# Thing_Plus_ESP32_C6.net
KiCad netlist of a schematic drawn in EAGLE
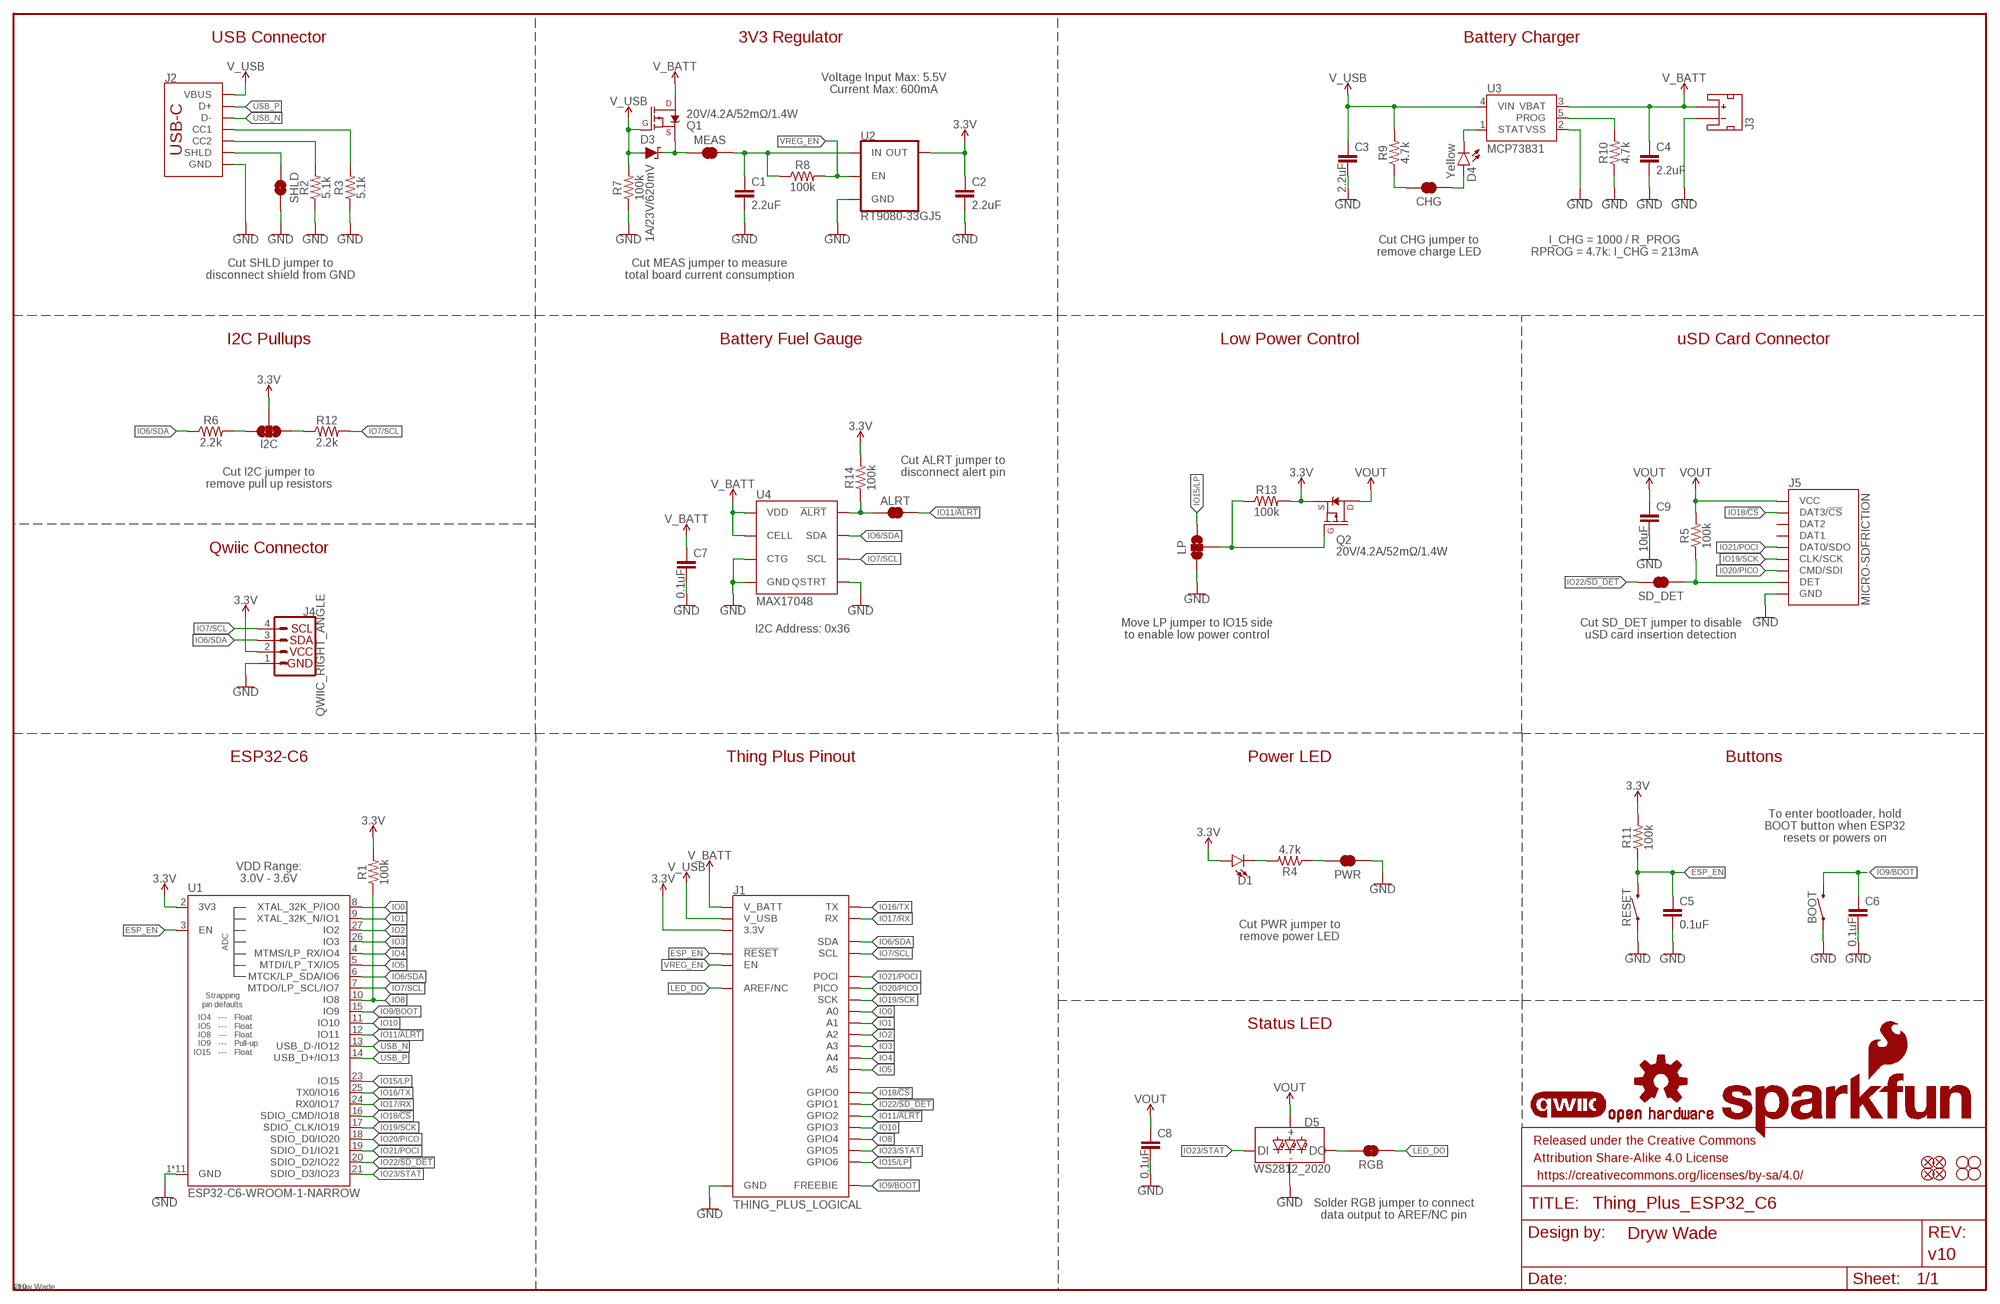
[diagram p0: schematic, sheet 1]

(export (version "E")
  (design (tool "Eeschema 10.0.6"))
  (components
    (comp (ref "ALRT")
      (value "JUMPER-SMT_2_NC_TRACE_SILK")
      (footprint "eagle-import:SMT-JUMPER_2_NC_TRACE_SILK")
      (libsource (lib "eagle-import") (part "JUMPER-SMT_2_NC_TRACE_SILK"))
    )
    (comp (ref "BOOT")
      (value "MOMENTARY-SWITCH-SPST-SMD-4.6X2.8MM")
      (footprint "eagle-import:TACTILE_SWITCH_SMD_4.6X2.8MM")
      (libsource (lib "eagle-import") (part "MOMENTARY-SWITCH-SPST-SMD-4.6X2.8MM"))
    )
    (comp (ref "C1")
      (value "2.2uF")
      (footprint "eagle-import:0603")
      (libsource (lib "eagle-import") (part "2.2UF-0603-10V-20%"))
    )
    (comp (ref "C2")
      (value "2.2uF")
      (footprint "eagle-import:0603")
      (libsource (lib "eagle-import") (part "2.2UF-0603-10V-20%"))
    )
    (comp (ref "C3")
      (value "2.2uF")
      (footprint "eagle-import:0603")
      (libsource (lib "eagle-import") (part "2.2UF-0603-10V-20%"))
    )
    (comp (ref "C4")
      (value "2.2uF")
      (footprint "eagle-import:0603")
      (libsource (lib "eagle-import") (part "2.2UF-0603-10V-20%"))
    )
    (comp (ref "C5")
      (value "0.1uF")
      (footprint "eagle-import:0603")
      (libsource (lib "eagle-import") (part "0.1UF-0603-25V-(+80/-20%)"))
    )
    (comp (ref "C6")
      (value "0.1uF")
      (footprint "eagle-import:0603")
      (libsource (lib "eagle-import") (part "0.1UF-0603-25V-(+80/-20%)"))
    )
    (comp (ref "C7")
      (value "0.1uF")
      (footprint "eagle-import:0603")
      (libsource (lib "eagle-import") (part "0.1UF-0603-25V-(+80/-20%)"))
    )
    (comp (ref "C8")
      (value "0.1uF")
      (footprint "eagle-import:0603")
      (libsource (lib "eagle-import") (part "0.1UF-0603-25V-(+80/-20%)"))
    )
    (comp (ref "C9")
      (value "10uF")
      (footprint "eagle-import:0603")
      (libsource (lib "eagle-import") (part "10UF-0603-6.3V-20%"))
    )
    (comp (ref "CHG")
      (value "JUMPER-SMT_2_NC_TRACE_SILK")
      (footprint "eagle-import:SMT-JUMPER_2_NC_TRACE_SILK")
      (libsource (lib "eagle-import") (part "JUMPER-SMT_2_NC_TRACE_SILK"))
    )
    (comp (ref "D1")
      (value "LED-RED_0603-KB")
      (footprint "eagle-import:LED-0603")
      (libsource (lib "eagle-import") (part "LED-RED_0603-KB"))
    )
    (comp (ref "D3")
      (value "1A/23V/620mV")
      (footprint "eagle-import:SOD-323")
      (libsource (lib "eagle-import") (part "DIODE-SCHOTTKY-BAT20J"))
    )
    (comp (ref "D4")
      (value "Yellow")
      (footprint "eagle-import:LED-0603")
      (libsource (lib "eagle-import") (part "LED-YELLOW0603"))
    )
    (comp (ref "D5")
      (value "WS2812_2020")
      (footprint "eagle-import:WS2812-2020")
      (libsource (lib "eagle-import") (part "WS2812_2020"))
    )
    (comp (ref "FD1")
      (value "FIDUCIALUFIDUCIAL")
      (footprint "eagle-import:FIDUCIAL-MICRO")
      (libsource (lib "eagle-import") (part "FIDUCIALUFIDUCIAL"))
    )
    (comp (ref "FD2")
      (value "FIDUCIALUFIDUCIAL")
      (footprint "eagle-import:FIDUCIAL-MICRO")
      (libsource (lib "eagle-import") (part "FIDUCIALUFIDUCIAL"))
    )
    (comp (ref "FD3")
      (value "FIDUCIALUFIDUCIAL")
      (footprint "eagle-import:FIDUCIAL-MICRO")
      (libsource (lib "eagle-import") (part "FIDUCIALUFIDUCIAL"))
    )
    (comp (ref "FD4")
      (value "FIDUCIALUFIDUCIAL")
      (footprint "eagle-import:FIDUCIAL-MICRO")
      (libsource (lib "eagle-import") (part "FIDUCIALUFIDUCIAL"))
    )
    (comp (ref "FRAME1")
      (value "FRAME-LEDGER")
      (footprint "eagle-import:CREATIVE_COMMONS")
      (fields (field (name "DESIGNER") "Dryw Wade") (field (name "REV") "v10"))
      (libsource (lib "eagle-import") (part "FRAME-LEDGER"))
    )
    (comp (ref "H1")
      (value "STAND-OFF")
      (footprint "eagle-import:STAND-OFF")
      (libsource (lib "eagle-import") (part "STAND-OFF"))
    )
    (comp (ref "H2")
      (value "STAND-OFF")
      (footprint "eagle-import:STAND-OFF")
      (libsource (lib "eagle-import") (part "STAND-OFF"))
    )
    (comp (ref "H3")
      (value "STAND-OFF")
      (footprint "eagle-import:STAND-OFF")
      (libsource (lib "eagle-import") (part "STAND-OFF"))
    )
    (comp (ref "H4")
      (value "STAND-OFF")
      (footprint "eagle-import:STAND-OFF")
      (libsource (lib "eagle-import") (part "STAND-OFF"))
    )
    (comp (ref "I2C")
      (value "JUMPER-SMT_3_2-NC_TRACE_SILK")
      (footprint "eagle-import:SMT-JUMPER_3_2-NC_TRACE_SILK")
      (libsource (lib "eagle-import") (part "JUMPER-SMT_3_2-NC_TRACE_SILK"))
    )
    (comp (ref "J1")
      (value "THING_PLUS_LOGICAL")
      (footprint "eagle-import:THING_PLUS")
      (libsource (lib "eagle-import") (part "THING_PLUS_LOGICAL"))
    )
    (comp (ref "J2")
      (value "USB_C_4-LAYER_PADS")
      (footprint "eagle-import:USB-C-16P_4LAYER-PADS")
      (libsource (lib "eagle-import") (part "USB_C_4-LAYER_PADS"))
    )
    (comp (ref "J3")
      (value "JST_2MM_MALE")
      (footprint "eagle-import:JST-2-SMD")
      (libsource (lib "eagle-import") (part "JST_2MM_MALE"))
    )
    (comp (ref "J4")
      (value "QWIIC_RIGHT_ANGLE")
      (footprint "eagle-import:JST04_1MM_RA")
      (libsource (lib "eagle-import") (part "QWIIC_CONNECTORJS-1MM"))
    )
    (comp (ref "J5")
      (value "MICRO-SDFRICTION")
      (footprint "eagle-import:MICROSD_TINY")
      (libsource (lib "eagle-import") (part "MICRO-SDFRICTION"))
    )
    (comp (ref "LOGO1")
      (value "SFE_LOGO_NAME_FLAME.1_INCH")
      (footprint "eagle-import:SFE_LOGO_NAME_FLAME_.1")
      (libsource (lib "eagle-import") (part "SFE_LOGO_NAME_FLAME.1_INCH"))
    )
    (comp (ref "LOGO2")
      (value "QWIIC_LOGO_4MM")
      (footprint "eagle-import:QWIIC_4MM")
      (libsource (lib "eagle-import") (part "QWIIC_LOGO_4MM"))
    )
    (comp (ref "LOGO3")
      (value "OSHW-LOGOM")
      (footprint "eagle-import:OSHW-LOGO-M")
      (libsource (lib "eagle-import") (part "OSHW-LOGOM"))
    )
    (comp (ref "LP")
      (value "JUMPER-SMT_3_1-NC_TRACE_SILK")
      (footprint "eagle-import:SMT-JUMPER_3_1-NC_TRACE_SILK")
      (libsource (lib "eagle-import") (part "JUMPER-SMT_3_1-NC_TRACE_SILK"))
    )
    (comp (ref "MEAS")
      (value "JUMPER-COMBO_2_NC_TRACE")
      (footprint "eagle-import:COMBO-JUMPER_2_NC_TRACE")
      (libsource (lib "eagle-import") (part "JUMPER-COMBO_2_NC_TRACE"))
    )
    (comp (ref "PWR")
      (value "JUMPER-SMT_2_NC_TRACE_SILK")
      (footprint "eagle-import:SMT-JUMPER_2_NC_TRACE_SILK")
      (libsource (lib "eagle-import") (part "JUMPER-SMT_2_NC_TRACE_SILK"))
    )
    (comp (ref "Q1")
      (value "20V/4.2A/52mΩ/1.4W")
      (footprint "eagle-import:SOT23-3")
      (libsource (lib "eagle-import") (part "MOSFET_PCH-DMG2305UX-7"))
    )
    (comp (ref "Q2")
      (value "20V/4.2A/52mΩ/1.4W")
      (footprint "eagle-import:SOT23-3")
      (libsource (lib "eagle-import") (part "MOSFET_PCH-DMG2305UX-7"))
    )
    (comp (ref "R1")
      (value "100k")
      (footprint "eagle-import:0603")
      (libsource (lib "eagle-import") (part "100KOHM-0603-1/10W-1%"))
    )
    (comp (ref "R2")
      (value "5.1k")
      (footprint "eagle-import:0603")
      (libsource (lib "eagle-import") (part "5.1KOHM5.1KOHM-0603-1/10W-1%"))
    )
    (comp (ref "R3")
      (value "5.1k")
      (footprint "eagle-import:0603")
      (libsource (lib "eagle-import") (part "5.1KOHM5.1KOHM-0603-1/10W-1%"))
    )
    (comp (ref "R4")
      (value "4.7k")
      (footprint "eagle-import:0603")
      (libsource (lib "eagle-import") (part "4.7KOHM-0603-1/10W-1%"))
    )
    (comp (ref "R5")
      (value "100k")
      (footprint "eagle-import:0603")
      (libsource (lib "eagle-import") (part "100KOHM-0603-1/10W-1%"))
    )
    (comp (ref "R6")
      (value "2.2k")
      (footprint "eagle-import:0603")
      (libsource (lib "eagle-import") (part "2.2KOHM-0603-1/10W-1%"))
    )
    (comp (ref "R7")
      (value "100k")
      (footprint "eagle-import:0603")
      (libsource (lib "eagle-import") (part "100KOHM-0603-1/10W-1%"))
    )
    (comp (ref "R8")
      (value "100k")
      (footprint "eagle-import:0603")
      (libsource (lib "eagle-import") (part "100KOHM-0603-1/10W-1%"))
    )
    (comp (ref "R9")
      (value "4.7k")
      (footprint "eagle-import:0603")
      (libsource (lib "eagle-import") (part "4.7KOHM-0603-1/10W-1%"))
    )
    (comp (ref "R10")
      (value "4.7k")
      (footprint "eagle-import:0603")
      (libsource (lib "eagle-import") (part "4.7KOHM-0603-1/10W-1%"))
    )
    (comp (ref "R11")
      (value "100k")
      (footprint "eagle-import:0603")
      (libsource (lib "eagle-import") (part "100KOHM-0603-1/10W-1%"))
    )
    (comp (ref "R12")
      (value "2.2k")
      (footprint "eagle-import:0603")
      (libsource (lib "eagle-import") (part "2.2KOHM-0603-1/10W-1%"))
    )
    (comp (ref "R13")
      (value "100k")
      (footprint "eagle-import:0603")
      (libsource (lib "eagle-import") (part "100KOHM-0603-1/10W-1%"))
    )
    (comp (ref "R14")
      (value "100k")
      (footprint "eagle-import:0603")
      (libsource (lib "eagle-import") (part "100KOHM-0603-1/10W-1%"))
    )
    (comp (ref "RESET")
      (value "MOMENTARY-SWITCH-SPST-SMD-4.6X2.8MM")
      (footprint "eagle-import:TACTILE_SWITCH_SMD_4.6X2.8MM")
      (libsource (lib "eagle-import") (part "MOMENTARY-SWITCH-SPST-SMD-4.6X2.8MM"))
    )
    (comp (ref "RGB")
      (value "JUMPER-SMT_2_NO_SILK")
      (footprint "eagle-import:SMT-JUMPER_2_NO_SILK")
      (libsource (lib "eagle-import") (part "JUMPER-SMT_2_NO_SILK"))
    )
    (comp (ref "SD_DET")
      (value "JUMPER-SMT_2_NC_TRACE_SILK")
      (footprint "eagle-import:SMT-JUMPER_2_NC_TRACE_SILK")
      (libsource (lib "eagle-import") (part "JUMPER-SMT_2_NC_TRACE_SILK"))
    )
    (comp (ref "SHLD")
      (value "JUMPER-SMT_2_NC_TRACE_SILK")
      (footprint "eagle-import:SMT-JUMPER_2_NC_TRACE_SILK")
      (libsource (lib "eagle-import") (part "JUMPER-SMT_2_NC_TRACE_SILK"))
    )
    (comp (ref "U1")
      (value "ESP32-C6-WROOM-1-NARROW")
      (footprint "eagle-import:ESP32-C6-WROOM-1-NARROW")
      (libsource (lib "eagle-import") (part "ESP32-C6-WROOM-1-NARROW"))
    )
    (comp (ref "U2")
      (value "RT9080-33GJ5")
      (footprint "eagle-import:SOT23-5")
      (libsource (lib "eagle-import") (part "V_REG_RT9080"))
    )
    (comp (ref "U3")
      (value "MCP73831")
      (footprint "eagle-import:SOT23-5")
      (libsource (lib "eagle-import") (part "MCP73831"))
    )
    (comp (ref "U4")
      (value "MAX17048")
      (footprint "eagle-import:DFN-8")
      (libsource (lib "eagle-import") (part "MAX17048DFN8"))
    )
  )
  (nets
    (net (code "1") (name "/IO11{slash}~{ALRT}") (class "Default")
      (node (ref "ALRT") (pin "2") (pinfunction "2_2") (pintype "passive"))
      (node (ref "J1") (pin "7") (pinfunction "GPIO2_7") (pintype "bidirectional"))
      (node (ref "U1") (pin "12") (pinfunction "IO11_12") (pintype "bidirectional"))
    )
    (net (code "2") (name "/IO18{slash}~{CS}") (class "Default")
      (node (ref "J1") (pin "9") (pinfunction "GPIO0_9") (pintype "bidirectional"))
      (node (ref "J5") (pin "2") (pinfunction "DAT3/~{CS}_2") (pintype "bidirectional"))
      (node (ref "U1") (pin "16") (pinfunction "SDIO_CMD/IO18_16") (pintype "bidirectional"))
    )
    (net (code "3") (name "/IO22{slash}~{SD_DET}") (class "Default")
      (node (ref "J1") (pin "8") (pinfunction "GPIO1_8") (pintype "bidirectional"))
      (node (ref "SD_DET") (pin "2") (pinfunction "2_2") (pintype "passive"))
      (node (ref "U1") (pin "20") (pinfunction "SDIO_D2/IO22_20") (pintype "bidirectional"))
    )
    (net (code "4") (name "3.3V") (class "Default")
      (node (ref "C2") (pin "1") (pinfunction "1_1") (pintype "passive"))
      (node (ref "D1") (pin "A") (pinfunction "A_A") (pintype "passive"))
      (node (ref "I2C") (pin "2") (pinfunction "2_2") (pintype "passive"))
      (node (ref "J1") (pin "27") (pinfunction "3.3V_27") (pintype "bidirectional"))
      (node (ref "J4") (pin "2") (pinfunction "2_2") (pintype "power_in"))
      (node (ref "Q2") (pin "2") (pinfunction "S_2") (pintype "bidirectional"))
      (node (ref "R1") (pin "2") (pinfunction "2_2") (pintype "passive"))
      (node (ref "R11") (pin "2") (pinfunction "2_2") (pintype "passive"))
      (node (ref "R13") (pin "2") (pinfunction "2_2") (pintype "passive"))
      (node (ref "R14") (pin "2") (pinfunction "2_2") (pintype "passive"))
      (node (ref "U1") (pin "2") (pinfunction "3V3_2") (pintype "bidirectional"))
      (node (ref "U2") (pin "5") (pinfunction "OUT_5") (pintype "passive"))
    )
    (net (code "5") (name "ESP_EN") (class "Default")
      (node (ref "C5") (pin "1") (pinfunction "1_1") (pintype "passive"))
      (node (ref "J1") (pin "28") (pinfunction "~{RESET}_28") (pintype "bidirectional"))
      (node (ref "R11") (pin "1") (pinfunction "1_1") (pintype "passive"))
      (node (ref "RESET") (pin "3") (pinfunction "2_3") (pintype "passive"))
      (node (ref "RESET") (pin "4") (pinfunction "2_4") (pintype "passive"))
      (node (ref "U1") (pin "3") (pinfunction "EN_3") (pintype "bidirectional"))
    )
    (net (code "6") (name "GND") (class "Default")
      (node (ref "BOOT") (pin "1") (pinfunction "1_1") (pintype "passive"))
      (node (ref "BOOT") (pin "2") (pinfunction "1_2") (pintype "passive"))
      (node (ref "C1") (pin "2") (pinfunction "2_2") (pintype "passive"))
      (node (ref "C2") (pin "2") (pinfunction "2_2") (pintype "passive"))
      (node (ref "C3") (pin "2") (pinfunction "2_2") (pintype "passive"))
      (node (ref "C4") (pin "2") (pinfunction "2_2") (pintype "passive"))
      (node (ref "C5") (pin "2") (pinfunction "2_2") (pintype "passive"))
      (node (ref "C6") (pin "2") (pinfunction "2_2") (pintype "passive"))
      (node (ref "C7") (pin "2") (pinfunction "2_2") (pintype "passive"))
      (node (ref "C8") (pin "2") (pinfunction "2_2") (pintype "passive"))
      (node (ref "C9") (pin "2") (pinfunction "2_2") (pintype "passive"))
      (node (ref "D5") (pin "GND") (pinfunction "GND_GND") (pintype "bidirectional"))
      (node (ref "J1") (pin "25") (pinfunction "GND_25") (pintype "bidirectional"))
      (node (ref "J2") (pin "GND") (pinfunction "GND_GND") (pintype "bidirectional"))
      (node (ref "J2") (pin "GND2") (pinfunction "GND_GND2") (pintype "bidirectional"))
      (node (ref "J3") (pin "1") (pinfunction "-_1") (pintype "bidirectional"))
      (node (ref "J4") (pin "1") (pinfunction "1_1") (pintype "power_in"))
      (node (ref "J5") (pin "6") (pinfunction "GND_6") (pintype "bidirectional"))
      (node (ref "J5") (pin "GND1") (pinfunction "GND_GND1") (pintype "bidirectional"))
      (node (ref "J5") (pin "GND2") (pinfunction "GND_GND2") (pintype "bidirectional"))
      (node (ref "J5") (pin "GND3") (pinfunction "GND_GND3") (pintype "bidirectional"))
      (node (ref "J5") (pin "GND4") (pinfunction "GND_GND4") (pintype "bidirectional"))
      (node (ref "J5") (pin "GND5") (pinfunction "GND_GND5") (pintype "bidirectional"))
      (node (ref "J5") (pin "GND6") (pinfunction "GND_GND6") (pintype "bidirectional"))
      (node (ref "LP") (pin "3") (pinfunction "3_3") (pintype "passive"))
      (node (ref "PWR") (pin "1") (pinfunction "1_1") (pintype "passive"))
      (node (ref "R10") (pin "1") (pinfunction "1_1") (pintype "passive"))
      (node (ref "R2") (pin "1") (pinfunction "1_1") (pintype "passive"))
      (node (ref "R3") (pin "1") (pinfunction "1_1") (pintype "passive"))
      (node (ref "R7") (pin "1") (pinfunction "1_1") (pintype "passive"))
      (node (ref "RESET") (pin "1") (pinfunction "1_1") (pintype "passive"))
      (node (ref "RESET") (pin "2") (pinfunction "1_2") (pintype "passive"))
      (node (ref "SHLD") (pin "2") (pinfunction "2_2") (pintype "passive"))
      (node (ref "U1") (pin "1") (pinfunction "GND_1") (pintype "bidirectional"))
      (node (ref "U1") (pin "28") (pinfunction "GND_28") (pintype "bidirectional"))
      (node (ref "U1") (pin "29") (pinfunction "GND_29") (pintype "bidirectional"))
      (node (ref "U1") (pin "30") (pinfunction "GND_30") (pintype "bidirectional"))
      (node (ref "U1") (pin "31") (pinfunction "GND_31") (pintype "bidirectional"))
      (node (ref "U1") (pin "32") (pinfunction "GND_32") (pintype "bidirectional"))
      (node (ref "U1") (pin "33") (pinfunction "GND_33") (pintype "bidirectional"))
      (node (ref "U1") (pin "34") (pinfunction "GND_34") (pintype "bidirectional"))
      (node (ref "U1") (pin "35") (pinfunction "GND_35") (pintype "bidirectional"))
      (node (ref "U1") (pin "36") (pinfunction "GND_36") (pintype "bidirectional"))
      (node (ref "U1") (pin "37") (pinfunction "GND_37") (pintype "bidirectional"))
      (node (ref "U2") (pin "2") (pinfunction "GND_2") (pintype "input"))
      (node (ref "U3") (pin "2") (pinfunction "VSS_2") (pintype "power_in"))
      (node (ref "U4") (pin "1") (pinfunction "CTG_1") (pintype "input"))
      (node (ref "U4") (pin "4") (pinfunction "GND_4") (pintype "bidirectional"))
      (node (ref "U4") (pin "6") (pinfunction "QSTRT_6") (pintype "bidirectional"))
      (node (ref "U4") (pin "9") (pinfunction "GND_9") (pintype "bidirectional"))
    )
    (net (code "7") (name "IO0") (class "Default")
      (node (ref "J1") (pin "24") (pinfunction "A0_24") (pintype "bidirectional"))
      (node (ref "U1") (pin "8") (pinfunction "XTAL_32K_P/IO0_8") (pintype "bidirectional"))
    )
    (net (code "8") (name "IO1") (class "Default")
      (node (ref "J1") (pin "23") (pinfunction "A1_23") (pintype "bidirectional"))
      (node (ref "U1") (pin "9") (pinfunction "XTAL_32K_N/IO1_9") (pintype "bidirectional"))
    )
    (net (code "9") (name "IO2") (class "Default")
      (node (ref "J1") (pin "22") (pinfunction "A2_22") (pintype "bidirectional"))
      (node (ref "U1") (pin "27") (pinfunction "IO2_27") (pintype "bidirectional"))
    )
    (net (code "10") (name "IO3") (class "Default")
      (node (ref "J1") (pin "21") (pinfunction "A3_21") (pintype "bidirectional"))
      (node (ref "U1") (pin "26") (pinfunction "IO3_26") (pintype "bidirectional"))
    )
    (net (code "11") (name "IO4") (class "Default")
      (node (ref "J1") (pin "20") (pinfunction "A4_20") (pintype "bidirectional"))
      (node (ref "U1") (pin "4") (pinfunction "MTMS/LP_RX/IO4_4") (pintype "bidirectional"))
    )
    (net (code "12") (name "IO5") (class "Default")
      (node (ref "J1") (pin "19") (pinfunction "A5_19") (pintype "bidirectional"))
      (node (ref "U1") (pin "5") (pinfunction "MTDI/LP_TX/IO5_5") (pintype "bidirectional"))
    )
    (net (code "13") (name "IO6{slash}SDA") (class "Default")
      (node (ref "J1") (pin "1") (pinfunction "SDA_1") (pintype "bidirectional"))
      (node (ref "J4") (pin "3") (pinfunction "3_3") (pintype "passive"))
      (node (ref "R6") (pin "1") (pinfunction "1_1") (pintype "passive"))
      (node (ref "U1") (pin "6") (pinfunction "MTCK/LP_SDA/IO6_6") (pintype "bidirectional"))
      (node (ref "U4") (pin "8") (pinfunction "SDA_8") (pintype "input"))
    )
    (net (code "14") (name "IO7{slash}SCL") (class "Default")
      (node (ref "J1") (pin "2") (pinfunction "SCL_2") (pintype "bidirectional"))
      (node (ref "J4") (pin "4") (pinfunction "4_4") (pintype "passive"))
      (node (ref "R12") (pin "2") (pinfunction "2_2") (pintype "passive"))
      (node (ref "U1") (pin "7") (pinfunction "MTDO/LP_SCL/IO7_7") (pintype "bidirectional"))
      (node (ref "U4") (pin "7") (pinfunction "SCL_7") (pintype "output"))
    )
    (net (code "15") (name "IO8") (class "Default")
      (node (ref "J1") (pin "5") (pinfunction "GPIO4_5") (pintype "bidirectional"))
      (node (ref "R1") (pin "1") (pinfunction "1_1") (pintype "passive"))
      (node (ref "U1") (pin "10") (pinfunction "IO8_10") (pintype "bidirectional"))
    )
    (net (code "16") (name "IO9{slash}BOOT") (class "Default")
      (node (ref "BOOT") (pin "3") (pinfunction "2_3") (pintype "passive"))
      (node (ref "BOOT") (pin "4") (pinfunction "2_4") (pintype "passive"))
      (node (ref "C6") (pin "1") (pinfunction "1_1") (pintype "passive"))
      (node (ref "J1") (pin "13") (pinfunction "FREEBIE_13") (pintype "bidirectional"))
      (node (ref "U1") (pin "15") (pinfunction "IO9_15") (pintype "bidirectional"))
    )
    (net (code "17") (name "IO10") (class "Default")
      (node (ref "J1") (pin "6") (pinfunction "GPIO3_6") (pintype "bidirectional"))
      (node (ref "U1") (pin "11") (pinfunction "IO10_11") (pintype "bidirectional"))
    )
    (net (code "18") (name "IO15{slash}LP") (class "Default")
      (node (ref "J1") (pin "3") (pinfunction "GPIO6_3") (pintype "bidirectional"))
      (node (ref "LP") (pin "1") (pinfunction "1_1") (pintype "passive"))
      (node (ref "U1") (pin "23") (pinfunction "IO15_23") (pintype "bidirectional"))
    )
    (net (code "19") (name "IO16{slash}TX") (class "Default")
      (node (ref "J1") (pin "14") (pinfunction "TX_14") (pintype "bidirectional"))
      (node (ref "U1") (pin "25") (pinfunction "TX0/IO16_25") (pintype "bidirectional"))
    )
    (net (code "20") (name "IO17{slash}RX") (class "Default")
      (node (ref "J1") (pin "15") (pinfunction "RX_15") (pintype "bidirectional"))
      (node (ref "U1") (pin "24") (pinfunction "RX0/IO17_24") (pintype "bidirectional"))
    )
    (net (code "21") (name "IO19{slash}SCK") (class "Default")
      (node (ref "J1") (pin "18") (pinfunction "SCK_18") (pintype "bidirectional"))
      (node (ref "J5") (pin "5") (pinfunction "CLK/SCK_5") (pintype "bidirectional"))
      (node (ref "U1") (pin "17") (pinfunction "SDIO_CLK/IO19_17") (pintype "bidirectional"))
    )
    (net (code "22") (name "IO20{slash}PICO") (class "Default")
      (node (ref "J1") (pin "17") (pinfunction "PICO_17") (pintype "bidirectional"))
      (node (ref "J5") (pin "3") (pinfunction "CMD/SDI_3") (pintype "bidirectional"))
      (node (ref "U1") (pin "18") (pinfunction "SDIO_D0/IO20_18") (pintype "bidirectional"))
    )
    (net (code "23") (name "IO21{slash}POCI") (class "Default")
      (node (ref "J1") (pin "16") (pinfunction "POCI_16") (pintype "bidirectional"))
      (node (ref "J5") (pin "7") (pinfunction "DAT0/SDO_7") (pintype "bidirectional"))
      (node (ref "U1") (pin "19") (pinfunction "SDIO_D1/IO21_19") (pintype "bidirectional"))
    )
    (net (code "24") (name "IO23{slash}STAT") (class "Default")
      (node (ref "D5") (pin "DI") (pinfunction "DI_DI") (pintype "bidirectional"))
      (node (ref "J1") (pin "4") (pinfunction "GPIO5_4") (pintype "bidirectional"))
      (node (ref "U1") (pin "21") (pinfunction "SDIO_D3/IO23_21") (pintype "bidirectional"))
    )
    (net (code "25") (name "LED_DO") (class "Default")
      (node (ref "J1") (pin "26") (pinfunction "AREF/NC_26") (pintype "bidirectional"))
      (node (ref "RGB") (pin "1") (pinfunction "1_1") (pintype "passive"))
    )
    (net (code "26") (name "Net-(CHG-Pad1)") (class "Default")
      (node (ref "CHG") (pin "1") (pinfunction "1_1") (pintype "passive"))
      (node (ref "D4") (pin "A") (pinfunction "A_A") (pintype "passive"))
    )
    (net (code "27") (name "Net-(CHG-Pad2)") (class "Default")
      (node (ref "CHG") (pin "2") (pinfunction "2_2") (pintype "passive"))
      (node (ref "R9") (pin "1") (pinfunction "1_1") (pintype "passive"))
    )
    (net (code "28") (name "Net-(D1-PadC)") (class "Default")
      (node (ref "D1") (pin "C") (pinfunction "C_C") (pintype "passive"))
      (node (ref "R4") (pin "2") (pinfunction "2_2") (pintype "passive"))
    )
    (net (code "29") (name "Net-(D5-PadDO)") (class "Default")
      (node (ref "D5") (pin "DO") (pinfunction "DO_DO") (pintype "bidirectional"))
      (node (ref "RGB") (pin "2") (pinfunction "2_2") (pintype "passive"))
    )
    (net (code "30") (name "Net-(I2C-Pad1)") (class "Default")
      (node (ref "I2C") (pin "1") (pinfunction "1_1") (pintype "passive"))
      (node (ref "R12") (pin "1") (pinfunction "1_1") (pintype "passive"))
    )
    (net (code "31") (name "Net-(I2C-Pad3)") (class "Default")
      (node (ref "I2C") (pin "3") (pinfunction "3_3") (pintype "passive"))
      (node (ref "R6") (pin "2") (pinfunction "2_2") (pintype "passive"))
    )
    (net (code "32") (name "Net-(J2-CC1)") (class "Default")
      (node (ref "J2") (pin "A5") (pinfunction "CC1_A5") (pintype "bidirectional"))
      (node (ref "R3") (pin "2") (pinfunction "2_2") (pintype "passive"))
    )
    (net (code "33") (name "Net-(J2-CC2)") (class "Default")
      (node (ref "J2") (pin "B5") (pinfunction "CC2_B5") (pintype "bidirectional"))
      (node (ref "R2") (pin "2") (pinfunction "2_2") (pintype "passive"))
    )
    (net (code "34") (name "Net-(J2-SHLD-PadSHLD1)") (class "Default")
      (node (ref "J2") (pin "SHLD1") (pinfunction "SHLD_SHLD1") (pintype "bidirectional"))
      (node (ref "J2") (pin "SHLD2") (pinfunction "SHLD_SHLD2") (pintype "bidirectional"))
      (node (ref "J2") (pin "SHLD3") (pinfunction "SHLD_SHLD3") (pintype "bidirectional"))
      (node (ref "J2") (pin "SHLD4") (pinfunction "SHLD_SHLD4") (pintype "bidirectional"))
      (node (ref "SHLD") (pin "1") (pinfunction "1_1") (pintype "passive"))
    )
    (net (code "35") (name "Net-(J5-DET)") (class "Default")
      (node (ref "J5") (pin "9") (pinfunction "DET_9") (pintype "bidirectional"))
      (node (ref "R5") (pin "1") (pinfunction "1_1") (pintype "passive"))
      (node (ref "SD_DET") (pin "1") (pinfunction "1_1") (pintype "passive"))
    )
    (net (code "36") (name "Net-(PWR-Pad2)") (class "Default")
      (node (ref "PWR") (pin "2") (pinfunction "2_2") (pintype "passive"))
      (node (ref "R4") (pin "1") (pinfunction "1_1") (pintype "passive"))
    )
    (net (code "37") (name "Net-(Q1-S)") (class "Default")
      (node (ref "D3") (pin "C") (pinfunction "C_C") (pintype "passive"))
      (node (ref "MEAS") (pin "1") (pinfunction "1_1") (pintype "passive"))
      (node (ref "MEAS") (pin "3") (pinfunction "1_3") (pintype "passive"))
      (node (ref "Q1") (pin "2") (pinfunction "S_2") (pintype "bidirectional"))
    )
    (net (code "38") (name "Net-(Q2-G)") (class "Default")
      (node (ref "LP") (pin "2") (pinfunction "2_2") (pintype "passive"))
      (node (ref "Q2") (pin "1") (pinfunction "G_1") (pintype "bidirectional"))
      (node (ref "R13") (pin "1") (pinfunction "1_1") (pintype "passive"))
    )
    (net (code "39") (name "Net-(U2-IN)") (class "Default")
      (node (ref "C1") (pin "1") (pinfunction "1_1") (pintype "passive"))
      (node (ref "MEAS") (pin "2") (pinfunction "2_2") (pintype "passive"))
      (node (ref "MEAS") (pin "4") (pinfunction "2_4") (pintype "passive"))
      (node (ref "R8") (pin "1") (pinfunction "1_1") (pintype "passive"))
      (node (ref "U2") (pin "1") (pinfunction "IN_1") (pintype "input"))
    )
    (net (code "40") (name "Net-(U3-PROG)") (class "Default")
      (node (ref "R10") (pin "2") (pinfunction "2_2") (pintype "passive"))
      (node (ref "U3") (pin "5") (pinfunction "PROG_5") (pintype "input"))
    )
    (net (code "41") (name "Net-(U3-STAT)") (class "Default")
      (node (ref "D4") (pin "C") (pinfunction "C_C") (pintype "passive"))
      (node (ref "U3") (pin "1") (pinfunction "STAT_1") (pintype "output"))
    )
    (net (code "42") (name "Net-(U4-~{ALRT})") (class "Default")
      (node (ref "ALRT") (pin "1") (pinfunction "1_1") (pintype "passive"))
      (node (ref "R14") (pin "1") (pinfunction "1_1") (pintype "passive"))
      (node (ref "U4") (pin "5") (pinfunction "~{ALRT}_5") (pintype "bidirectional"))
    )
    (net (code "43") (name "USB_N") (class "Default")
      (node (ref "J2") (pin "A7") (pinfunction "D-_A7") (pintype "bidirectional"))
      (node (ref "J2") (pin "B7") (pinfunction "D-_B7") (pintype "bidirectional"))
      (node (ref "U1") (pin "13") (pinfunction "USB_D-/IO12_13") (pintype "bidirectional"))
    )
    (net (code "44") (name "USB_P") (class "Default")
      (node (ref "J2") (pin "A6") (pinfunction "D+_A6") (pintype "bidirectional"))
      (node (ref "J2") (pin "B6") (pinfunction "D+_B6") (pintype "bidirectional"))
      (node (ref "U1") (pin "14") (pinfunction "USB_D+/IO13_14") (pintype "bidirectional"))
    )
    (net (code "45") (name "VOUT") (class "Default")
      (node (ref "C8") (pin "1") (pinfunction "1_1") (pintype "passive"))
      (node (ref "C9") (pin "1") (pinfunction "1_1") (pintype "passive"))
      (node (ref "D5") (pin "VCC") (pinfunction "VCC_VCC") (pintype "bidirectional"))
      (node (ref "J5") (pin "4") (pinfunction "VCC_4") (pintype "bidirectional"))
      (node (ref "Q2") (pin "3") (pinfunction "D_3") (pintype "bidirectional"))
      (node (ref "R5") (pin "2") (pinfunction "2_2") (pintype "passive"))
    )
    (net (code "46") (name "VREG_EN") (class "Default")
      (node (ref "J1") (pin "11") (pinfunction "EN_11") (pintype "bidirectional"))
      (node (ref "R8") (pin "2") (pinfunction "2_2") (pintype "passive"))
      (node (ref "U2") (pin "3") (pinfunction "EN_3") (pintype "input"))
    )
    (net (code "47") (name "V_BATT") (class "Default")
      (node (ref "C4") (pin "1") (pinfunction "1_1") (pintype "passive"))
      (node (ref "C7") (pin "1") (pinfunction "1_1") (pintype "passive"))
      (node (ref "J1") (pin "12") (pinfunction "V_BATT_12") (pintype "bidirectional"))
      (node (ref "J3") (pin "2") (pinfunction "+_2") (pintype "bidirectional"))
      (node (ref "Q1") (pin "3") (pinfunction "D_3") (pintype "bidirectional"))
      (node (ref "U3") (pin "3") (pinfunction "VBAT_3") (pintype "power_in"))
      (node (ref "U4") (pin "2") (pinfunction "CELL_2") (pintype "input"))
      (node (ref "U4") (pin "3") (pinfunction "VDD_3") (pintype "bidirectional"))
    )
    (net (code "48") (name "V_USB") (class "Default")
      (node (ref "C3") (pin "1") (pinfunction "1_1") (pintype "passive"))
      (node (ref "D3") (pin "A") (pinfunction "A_A") (pintype "passive"))
      (node (ref "J1") (pin "10") (pinfunction "V_USB_10") (pintype "bidirectional"))
      (node (ref "J2") (pin "VBUS1") (pinfunction "VBUS_VBUS1") (pintype "bidirectional"))
      (node (ref "J2") (pin "VBUS2") (pinfunction "VBUS_VBUS2") (pintype "bidirectional"))
      (node (ref "Q1") (pin "1") (pinfunction "G_1") (pintype "bidirectional"))
      (node (ref "R7") (pin "2") (pinfunction "2_2") (pintype "passive"))
      (node (ref "R9") (pin "2") (pinfunction "2_2") (pintype "passive"))
      (node (ref "U3") (pin "4") (pinfunction "VIN_4") (pintype "power_in"))
    )
    (net (code "49") (name "unconnected-(J3-PAD1-PadNC1)") (class "Default")
      (node (ref "J3") (pin "NC1") (pinfunction "PAD1_NC1") (pintype "bidirectional"))
    )
    (net (code "50") (name "unconnected-(J3-PAD2-PadNC2)") (class "Default")
      (node (ref "J3") (pin "NC2") (pinfunction "PAD2_NC2") (pintype "bidirectional"))
    )
    (net (code "51") (name "unconnected-(J5-DAT1-Pad8)") (class "Default")
      (node (ref "J5") (pin "8") (pinfunction "DAT1_8") (pintype "bidirectional"))
    )
    (net (code "52") (name "unconnected-(J5-DAT2-Pad1)") (class "Default")
      (node (ref "J5") (pin "1") (pinfunction "DAT2_1") (pintype "bidirectional"))
    )
  )
)
